# SCHEMATIC_EP.net
KiCad netlist of a schematic drawn in EAGLE
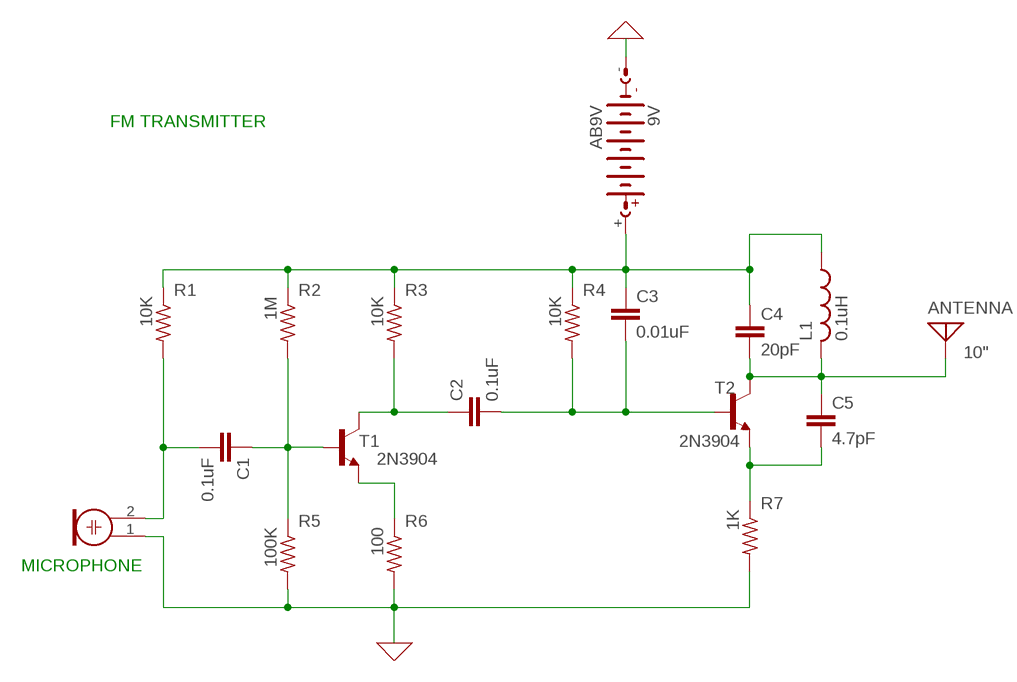
[diagram p0: schematic, sheet 1]

(export (version "E")
  (design (tool "Eeschema 10.0.6"))
  (components
    (comp (ref "9V")
      (value "AB9V")
      (footprint "eagle-import:AB9V")
      (libsource (lib "eagle-import") (part "AB9V"))
    )
    (comp (ref "ANTENNA")
      (value "10\"")
      (footprint "eagle-import:PAD-01")
      (libsource (lib "eagle-import") (part "ANTENNA"))
    )
    (comp (ref "C1")
      (value "0.1uF")
      (footprint "eagle-import:C2.5-2")
      (libsource (lib "eagle-import") (part "C2.5/2"))
    )
    (comp (ref "C2")
      (value "0.1uF")
      (footprint "eagle-import:C2.5-2")
      (libsource (lib "eagle-import") (part "C2.5/2"))
    )
    (comp (ref "C3")
      (value "0.01uF")
      (footprint "eagle-import:C2.5-2")
      (libsource (lib "eagle-import") (part "C2.5/2"))
    )
    (comp (ref "C4")
      (value "20pF")
      (footprint "eagle-import:C2.5-2")
      (libsource (lib "eagle-import") (part "C2.5/2"))
    )
    (comp (ref "C5")
      (value "4.7pF")
      (footprint "eagle-import:C2.5-2")
      (libsource (lib "eagle-import") (part "C2.5/2"))
    )
    (comp (ref "L1")
      (value "0.1uH")
      (footprint "eagle-import:0207_7")
      (libsource (lib "eagle-import") (part "L-US0207/7"))
    )
    (comp (ref "MICROPHONE")
      (value "ELECTRET_MICROPHON-F6050AP")
      (footprint "eagle-import:F6050AP")
      (libsource (lib "eagle-import") (part "ELECTRET_MICROPHON-F6050AP"))
    )
    (comp (ref "R1")
      (value "10K")
      (footprint "eagle-import:R0603")
      (libsource (lib "eagle-import") (part "R-US_R0603"))
    )
    (comp (ref "R2")
      (value "1M")
      (footprint "eagle-import:R0603")
      (libsource (lib "eagle-import") (part "R-US_R0603"))
    )
    (comp (ref "R3")
      (value "10K")
      (footprint "eagle-import:R0603")
      (libsource (lib "eagle-import") (part "R-US_R0603"))
    )
    (comp (ref "R4")
      (value "10K")
      (footprint "eagle-import:R0603")
      (libsource (lib "eagle-import") (part "R-US_R0603"))
    )
    (comp (ref "R5")
      (value "100K")
      (footprint "eagle-import:R0603")
      (libsource (lib "eagle-import") (part "R-US_R0603"))
    )
    (comp (ref "R6")
      (value "100")
      (footprint "eagle-import:R0603")
      (libsource (lib "eagle-import") (part "R-US_R0603"))
    )
    (comp (ref "R7")
      (value "1K")
      (footprint "eagle-import:R0603")
      (libsource (lib "eagle-import") (part "R-US_R0603"))
    )
    (comp (ref "T1")
      (value "2N3904")
      (footprint "eagle-import:TO92")
      (libsource (lib "eagle-import") (part "2N3904"))
    )
    (comp (ref "T2")
      (value "2N3904")
      (footprint "eagle-import:TO92")
      (libsource (lib "eagle-import") (part "2N3904"))
    )
  )
  (nets
    (net (code "1") (name "GND") (class "Default")
      (node (ref "9V") (pin "-") (pinfunction "-_-") (pintype "passive"))
      (node (ref "MICROPHONE") (pin "1") (pinfunction "1_1") (pintype "passive"))
      (node (ref "R5") (pin "2") (pinfunction "2_2") (pintype "passive"))
      (node (ref "R6") (pin "2") (pinfunction "2_2") (pintype "passive"))
      (node (ref "R7") (pin "2") (pinfunction "2_2") (pintype "passive"))
    )
    (net (code "2") (name "Net-(9V-Pad+)") (class "Default")
      (node (ref "9V") (pin "+") (pinfunction "+_+") (pintype "passive"))
      (node (ref "C3") (pin "1") (pinfunction "1_1") (pintype "passive"))
      (node (ref "C4") (pin "1") (pinfunction "1_1") (pintype "passive"))
      (node (ref "L1") (pin "1") (pinfunction "1_1") (pintype "passive"))
      (node (ref "R1") (pin "1") (pinfunction "1_1") (pintype "passive"))
      (node (ref "R2") (pin "1") (pinfunction "1_1") (pintype "passive"))
      (node (ref "R3") (pin "1") (pinfunction "1_1") (pintype "passive"))
      (node (ref "R4") (pin "1") (pinfunction "1_1") (pintype "passive"))
    )
    (net (code "3") (name "Net-(C1-Pad2)") (class "Default")
      (node (ref "C1") (pin "2") (pinfunction "2_2") (pintype "passive"))
      (node (ref "MICROPHONE") (pin "2") (pinfunction "2_2") (pintype "passive"))
      (node (ref "R1") (pin "2") (pinfunction "2_2") (pintype "passive"))
    )
    (net (code "4") (name "Net-(T1-B)") (class "Default")
      (node (ref "C1") (pin "1") (pinfunction "1_1") (pintype "passive"))
      (node (ref "R2") (pin "2") (pinfunction "2_2") (pintype "passive"))
      (node (ref "R5") (pin "1") (pinfunction "1_1") (pintype "passive"))
      (node (ref "T1") (pin "2") (pinfunction "B_2") (pintype "passive"))
    )
    (net (code "5") (name "Net-(T1-C)") (class "Default")
      (node (ref "C2") (pin "1") (pinfunction "1_1") (pintype "passive"))
      (node (ref "R3") (pin "2") (pinfunction "2_2") (pintype "passive"))
      (node (ref "T1") (pin "1") (pinfunction "C_1") (pintype "passive"))
    )
    (net (code "6") (name "Net-(T1-E)") (class "Default")
      (node (ref "R6") (pin "1") (pinfunction "1_1") (pintype "passive"))
      (node (ref "T1") (pin "3") (pinfunction "E_3") (pintype "passive"))
    )
    (net (code "7") (name "Net-(T2-B)") (class "Default")
      (node (ref "C2") (pin "2") (pinfunction "2_2") (pintype "passive"))
      (node (ref "C3") (pin "2") (pinfunction "2_2") (pintype "passive"))
      (node (ref "R4") (pin "2") (pinfunction "2_2") (pintype "passive"))
      (node (ref "T2") (pin "2") (pinfunction "B_2") (pintype "passive"))
    )
    (net (code "8") (name "Net-(T2-C)") (class "Default")
      (node (ref "ANTENNA") (pin "1") (pinfunction "1_1") (pintype "output"))
      (node (ref "C4") (pin "2") (pinfunction "2_2") (pintype "passive"))
      (node (ref "C5") (pin "1") (pinfunction "1_1") (pintype "passive"))
      (node (ref "L1") (pin "2") (pinfunction "2_2") (pintype "passive"))
      (node (ref "T2") (pin "1") (pinfunction "C_1") (pintype "passive"))
    )
    (net (code "9") (name "Net-(T2-E)") (class "Default")
      (node (ref "C5") (pin "2") (pinfunction "2_2") (pintype "passive"))
      (node (ref "R7") (pin "1") (pinfunction "1_1") (pintype "passive"))
      (node (ref "T2") (pin "3") (pinfunction "E_3") (pintype "passive"))
    )
  )
)
